# schematic.net
KiCad netlist of a schematic drawn in EAGLE
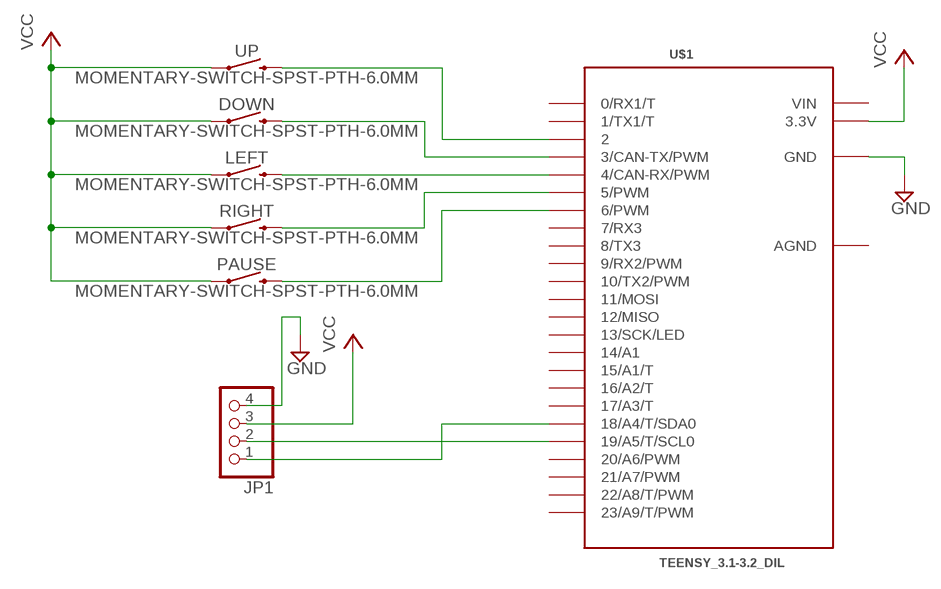
[diagram p0: schematic, sheet 1]

(export (version "E")
  (design (tool "Eeschema 10.0.6"))
  (components
    (comp (ref "DOWN")
      (value "MOMENTARY-SWITCH-SPST-PTH-6.0MM")
      (footprint "eagle-import:TACTILE_SWITCH_PTH_6.0MM")
      (libsource (lib "eagle-import") (part "MOMENTARY-SWITCH-SPST-PTH-6.0MM"))
    )
    (comp (ref "JP1")
      (value "PINHD-1X4")
      (footprint "eagle-import:1X04")
      (libsource (lib "eagle-import") (part "PINHD-1X4"))
    )
    (comp (ref "LEFT")
      (value "MOMENTARY-SWITCH-SPST-PTH-6.0MM")
      (footprint "eagle-import:TACTILE_SWITCH_PTH_6.0MM")
      (libsource (lib "eagle-import") (part "MOMENTARY-SWITCH-SPST-PTH-6.0MM"))
    )
    (comp (ref "PAUSE")
      (value "MOMENTARY-SWITCH-SPST-PTH-6.0MM")
      (footprint "eagle-import:TACTILE_SWITCH_PTH_6.0MM")
      (libsource (lib "eagle-import") (part "MOMENTARY-SWITCH-SPST-PTH-6.0MM"))
    )
    (comp (ref "RIGHT")
      (value "MOMENTARY-SWITCH-SPST-PTH-6.0MM")
      (footprint "eagle-import:TACTILE_SWITCH_PTH_6.0MM")
      (libsource (lib "eagle-import") (part "MOMENTARY-SWITCH-SPST-PTH-6.0MM"))
    )
    (comp (ref "U$1")
      (value "TEENSY_3.1-3.2_DIL")
      (footprint "eagle-import:TEENSY_3.0-3.2&LC_DIL")
      (libsource (lib "eagle-import") (part "TEENSY_3.1-3.2_DIL"))
    )
    (comp (ref "UP")
      (value "MOMENTARY-SWITCH-SPST-PTH-6.0MM")
      (footprint "eagle-import:TACTILE_SWITCH_PTH_6.0MM")
      (libsource (lib "eagle-import") (part "MOMENTARY-SWITCH-SPST-PTH-6.0MM"))
    )
  )
  (nets
    (net (code "1") (name "/AGND") (class "Default")
      (node (ref "U$1") (pin "AGND") (pinfunction "AGND_AGND") (pintype "power_in"))
    )
    (net (code "2") (name "/VIN") (class "Default")
      (node (ref "U$1") (pin "VIN") (pinfunction "VIN_VIN") (pintype "power_in"))
    )
    (net (code "3") (name "GND") (class "Default")
      (node (ref "JP1") (pin "4") (pinfunction "4_4") (pintype "passive"))
      (node (ref "U$1") (pin "GND") (pinfunction "GND_GND") (pintype "power_in"))
    )
    (net (code "4") (name "Net-(DOWN-2)") (class "Default")
      (node (ref "DOWN") (pin "3") (pinfunction "2_3") (pintype "passive"))
      (node (ref "U$1") (pin "3") (pinfunction "3/CAN-TX/PWM_3") (pintype "bidirectional"))
    )
    (net (code "5") (name "Net-(LEFT-2)") (class "Default")
      (node (ref "LEFT") (pin "3") (pinfunction "2_3") (pintype "passive"))
      (node (ref "U$1") (pin "4") (pinfunction "4/CAN-RX/PWM_4") (pintype "bidirectional"))
    )
    (net (code "6") (name "Net-(PAUSE-2)") (class "Default")
      (node (ref "PAUSE") (pin "3") (pinfunction "2_3") (pintype "passive"))
      (node (ref "U$1") (pin "6") (pinfunction "6/PWM_6") (pintype "bidirectional"))
    )
    (net (code "7") (name "Net-(RIGHT-2)") (class "Default")
      (node (ref "RIGHT") (pin "3") (pinfunction "2_3") (pintype "passive"))
      (node (ref "U$1") (pin "5") (pinfunction "5/PWM_5") (pintype "bidirectional"))
    )
    (net (code "8") (name "Net-(U$1-18{slash}A4{slash}T{slash}SDA0)") (class "Default")
      (node (ref "JP1") (pin "1") (pinfunction "1_1") (pintype "passive"))
      (node (ref "U$1") (pin "18/A4") (pinfunction "18/A4/T/SDA0_18/A4") (pintype "bidirectional"))
    )
    (net (code "9") (name "Net-(U$1-19{slash}A5{slash}T{slash}SCL0)") (class "Default")
      (node (ref "JP1") (pin "2") (pinfunction "2_2") (pintype "passive"))
      (node (ref "U$1") (pin "19/A5") (pinfunction "19/A5/T/SCL0_19/A5") (pintype "bidirectional"))
    )
    (net (code "10") (name "Net-(UP-2)") (class "Default")
      (node (ref "U$1") (pin "2") (pinfunction "2_2") (pintype "bidirectional"))
      (node (ref "UP") (pin "3") (pinfunction "2_3") (pintype "passive"))
    )
    (net (code "11") (name "VCC") (class "Default")
      (node (ref "DOWN") (pin "1") (pinfunction "1_1") (pintype "passive"))
      (node (ref "JP1") (pin "3") (pinfunction "3_3") (pintype "passive"))
      (node (ref "LEFT") (pin "1") (pinfunction "1_1") (pintype "passive"))
      (node (ref "PAUSE") (pin "1") (pinfunction "1_1") (pintype "passive"))
      (node (ref "RIGHT") (pin "1") (pinfunction "1_1") (pintype "passive"))
      (node (ref "U$1") (pin "3.3V") (pinfunction "3.3V_3.3V") (pintype "power_in"))
      (node (ref "UP") (pin "1") (pinfunction "1_1") (pintype "passive"))
    )
    (net (code "12") (name "unconnected-(U$1-0{slash}RX1{slash}T-Pad0)") (class "Default")
      (node (ref "U$1") (pin "0") (pinfunction "0/RX1/T_0") (pintype "bidirectional"))
    )
    (net (code "13") (name "unconnected-(U$1-1{slash}TX1{slash}T-Pad1)") (class "Default")
      (node (ref "U$1") (pin "1") (pinfunction "1/TX1/T_1") (pintype "bidirectional"))
    )
    (net (code "14") (name "unconnected-(U$1-7{slash}RX3-Pad7)") (class "Default")
      (node (ref "U$1") (pin "7") (pinfunction "7/RX3_7") (pintype "bidirectional"))
    )
    (net (code "15") (name "unconnected-(U$1-8{slash}TX3-Pad8)") (class "Default")
      (node (ref "U$1") (pin "8") (pinfunction "8/TX3_8") (pintype "bidirectional"))
    )
    (net (code "16") (name "unconnected-(U$1-9{slash}RX2{slash}PWM-Pad9)") (class "Default")
      (node (ref "U$1") (pin "9") (pinfunction "9/RX2/PWM_9") (pintype "bidirectional"))
    )
    (net (code "17") (name "unconnected-(U$1-10{slash}TX2{slash}PWM-Pad10)") (class "Default")
      (node (ref "U$1") (pin "10") (pinfunction "10/TX2/PWM_10") (pintype "bidirectional"))
    )
    (net (code "18") (name "unconnected-(U$1-11{slash}MOSI-Pad11)") (class "Default")
      (node (ref "U$1") (pin "11") (pinfunction "11/MOSI_11") (pintype "bidirectional"))
    )
    (net (code "19") (name "unconnected-(U$1-12{slash}MISO-Pad12)") (class "Default")
      (node (ref "U$1") (pin "12") (pinfunction "12/MISO_12") (pintype "bidirectional"))
    )
    (net (code "20") (name "unconnected-(U$1-13{slash}SCK{slash}LED-Pad13)") (class "Default")
      (node (ref "U$1") (pin "13") (pinfunction "13/SCK/LED_13") (pintype "bidirectional"))
    )
    (net (code "21") (name "unconnected-(U$1-14{slash}A1-Pad14{slash}A0)") (class "Default")
      (node (ref "U$1") (pin "14/A0") (pinfunction "14/A1_14/A0") (pintype "bidirectional"))
    )
    (net (code "22") (name "unconnected-(U$1-15{slash}A1{slash}T-Pad15{slash}A1)") (class "Default")
      (node (ref "U$1") (pin "15/A1") (pinfunction "15/A1/T_15/A1") (pintype "bidirectional"))
    )
    (net (code "23") (name "unconnected-(U$1-16{slash}A2{slash}T-Pad16{slash}A2)") (class "Default")
      (node (ref "U$1") (pin "16/A2") (pinfunction "16/A2/T_16/A2") (pintype "bidirectional"))
    )
    (net (code "24") (name "unconnected-(U$1-17{slash}A3{slash}T-Pad17{slash}A3)") (class "Default")
      (node (ref "U$1") (pin "17/A3") (pinfunction "17/A3/T_17/A3") (pintype "bidirectional"))
    )
    (net (code "25") (name "unconnected-(U$1-20{slash}A6{slash}PWM-Pad20{slash}A6)") (class "Default")
      (node (ref "U$1") (pin "20/A6") (pinfunction "20/A6/PWM_20/A6") (pintype "bidirectional"))
    )
    (net (code "26") (name "unconnected-(U$1-21{slash}A7{slash}PWM-Pad21{slash}A7)") (class "Default")
      (node (ref "U$1") (pin "21/A7") (pinfunction "21/A7/PWM_21/A7") (pintype "bidirectional"))
    )
    (net (code "27") (name "unconnected-(U$1-22{slash}A8{slash}T{slash}PWM-Pad22{slash}A8)") (class "Default")
      (node (ref "U$1") (pin "22/A8") (pinfunction "22/A8/T/PWM_22/A8") (pintype "bidirectional"))
    )
    (net (code "28") (name "unconnected-(U$1-23{slash}A9{slash}T{slash}PWM-Pad23{slash}A9)") (class "Default")
      (node (ref "U$1") (pin "23/A9") (pinfunction "23/A9/T/PWM_23/A9") (pintype "bidirectional"))
    )
  )
)
